# Gameboy_Cartridge.net
KiCad netlist of a schematic drawn in EAGLE
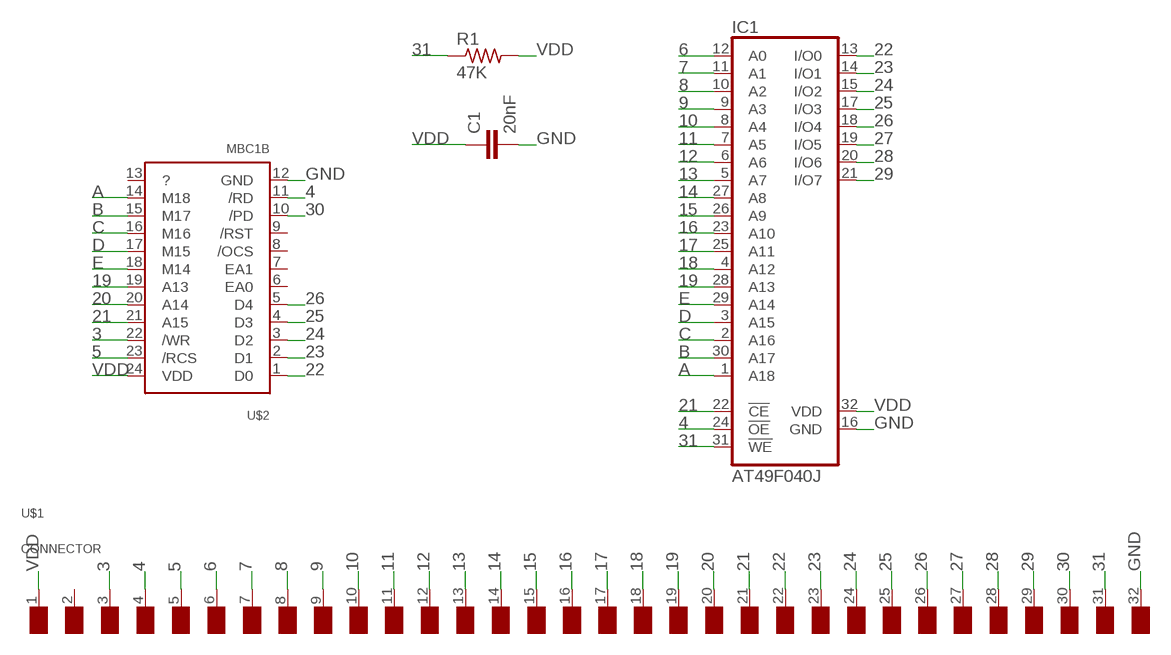
[diagram p0: schematic, sheet 1]

(export (version "E")
  (design (tool "Eeschema 10.0.6"))
  (components
    (comp (ref "C1")
      (value "20nF")
      (footprint "eagle-import:C0805")
      (libsource (lib "eagle-import") (part "C-EUC0805"))
    )
    (comp (ref "IC1")
      (value "AT49F040J")
      (footprint "eagle-import:PLCC32R")
      (libsource (lib "eagle-import") (part "AT49F040J"))
    )
    (comp (ref "R1")
      (value "47K")
      (footprint "eagle-import:M0805")
      (libsource (lib "eagle-import") (part "R-US_M0805"))
    )
    (comp (ref "U$1")
      (value "CONNECTOR")
      (footprint "eagle-import:CONNECTOR")
      (libsource (lib "eagle-import") (part "CONNECTOR"))
    )
    (comp (ref "U$2")
      (value "MBC1B")
      (footprint "eagle-import:MBC1B")
      (libsource (lib "eagle-import") (part "MBC1B"))
    )
  )
  (nets
    (net (code "1") (name "/3") (class "Default")
      (node (ref "U$1") (pin "3") (pinfunction "/WR_3") (pintype "bidirectional"))
      (node (ref "U$2") (pin "22") (pinfunction "/WR_22") (pintype "bidirectional"))
    )
    (net (code "2") (name "/4") (class "Default")
      (node (ref "IC1") (pin "24") (pinfunction "~{OE}_24") (pintype "input"))
      (node (ref "U$1") (pin "4") (pinfunction "/RD_4") (pintype "bidirectional"))
      (node (ref "U$2") (pin "11") (pinfunction "/RD_11") (pintype "bidirectional"))
    )
    (net (code "3") (name "/5") (class "Default")
      (node (ref "U$1") (pin "5") (pinfunction "/RCS_5") (pintype "bidirectional"))
      (node (ref "U$2") (pin "23") (pinfunction "/RCS_23") (pintype "bidirectional"))
    )
    (net (code "4") (name "/6") (class "Default")
      (node (ref "IC1") (pin "12") (pinfunction "A0_12") (pintype "input"))
      (node (ref "U$1") (pin "6") (pinfunction "A0_6") (pintype "bidirectional"))
    )
    (net (code "5") (name "/7") (class "Default")
      (node (ref "IC1") (pin "11") (pinfunction "A1_11") (pintype "input"))
      (node (ref "U$1") (pin "7") (pinfunction "A1_7") (pintype "bidirectional"))
    )
    (net (code "6") (name "/8") (class "Default")
      (node (ref "IC1") (pin "10") (pinfunction "A2_10") (pintype "input"))
      (node (ref "U$1") (pin "8") (pinfunction "A2_8") (pintype "bidirectional"))
    )
    (net (code "7") (name "/9") (class "Default")
      (node (ref "IC1") (pin "9") (pinfunction "A3_9") (pintype "input"))
      (node (ref "U$1") (pin "9") (pinfunction "A3_9") (pintype "bidirectional"))
    )
    (net (code "8") (name "/10") (class "Default")
      (node (ref "IC1") (pin "8") (pinfunction "A4_8") (pintype "input"))
      (node (ref "U$1") (pin "10") (pinfunction "A4_10") (pintype "bidirectional"))
    )
    (net (code "9") (name "/11") (class "Default")
      (node (ref "IC1") (pin "7") (pinfunction "A5_7") (pintype "input"))
      (node (ref "U$1") (pin "11") (pinfunction "A5_11") (pintype "bidirectional"))
    )
    (net (code "10") (name "/12") (class "Default")
      (node (ref "IC1") (pin "6") (pinfunction "A6_6") (pintype "input"))
      (node (ref "U$1") (pin "12") (pinfunction "A6_12") (pintype "bidirectional"))
    )
    (net (code "11") (name "/13") (class "Default")
      (node (ref "IC1") (pin "5") (pinfunction "A7_5") (pintype "input"))
      (node (ref "U$1") (pin "13") (pinfunction "A7_13") (pintype "bidirectional"))
    )
    (net (code "12") (name "/14") (class "Default")
      (node (ref "IC1") (pin "27") (pinfunction "A8_27") (pintype "input"))
      (node (ref "U$1") (pin "14") (pinfunction "A8_14") (pintype "bidirectional"))
    )
    (net (code "13") (name "/15") (class "Default")
      (node (ref "IC1") (pin "26") (pinfunction "A9_26") (pintype "input"))
      (node (ref "U$1") (pin "15") (pinfunction "A9_15") (pintype "bidirectional"))
    )
    (net (code "14") (name "/16") (class "Default")
      (node (ref "IC1") (pin "23") (pinfunction "A10_23") (pintype "input"))
      (node (ref "U$1") (pin "16") (pinfunction "A10_16") (pintype "bidirectional"))
    )
    (net (code "15") (name "/17") (class "Default")
      (node (ref "IC1") (pin "25") (pinfunction "A11_25") (pintype "input"))
      (node (ref "U$1") (pin "17") (pinfunction "A11_17") (pintype "bidirectional"))
    )
    (net (code "16") (name "/18") (class "Default")
      (node (ref "IC1") (pin "4") (pinfunction "A12_4") (pintype "input"))
      (node (ref "U$1") (pin "18") (pinfunction "A12_18") (pintype "bidirectional"))
    )
    (net (code "17") (name "/19") (class "Default")
      (node (ref "IC1") (pin "28") (pinfunction "A13_28") (pintype "input"))
      (node (ref "U$1") (pin "19") (pinfunction "A13_19") (pintype "bidirectional"))
      (node (ref "U$2") (pin "19") (pinfunction "A13_19") (pintype "bidirectional"))
    )
    (net (code "18") (name "/20") (class "Default")
      (node (ref "U$1") (pin "20") (pinfunction "A14_20") (pintype "bidirectional"))
      (node (ref "U$2") (pin "20") (pinfunction "A14_20") (pintype "bidirectional"))
    )
    (net (code "19") (name "/21") (class "Default")
      (node (ref "IC1") (pin "22") (pinfunction "~{CE}_22") (pintype "input"))
      (node (ref "U$1") (pin "21") (pinfunction "A15_21") (pintype "bidirectional"))
      (node (ref "U$2") (pin "21") (pinfunction "A15_21") (pintype "bidirectional"))
    )
    (net (code "20") (name "/22") (class "Default")
      (node (ref "IC1") (pin "13") (pinfunction "I/O0_13") (pintype "tri_state"))
      (node (ref "U$1") (pin "22") (pinfunction "D0_22") (pintype "bidirectional"))
      (node (ref "U$2") (pin "1") (pinfunction "D0_1") (pintype "bidirectional"))
    )
    (net (code "21") (name "/23") (class "Default")
      (node (ref "IC1") (pin "14") (pinfunction "I/O1_14") (pintype "tri_state"))
      (node (ref "U$1") (pin "23") (pinfunction "D1_23") (pintype "bidirectional"))
      (node (ref "U$2") (pin "2") (pinfunction "D1_2") (pintype "bidirectional"))
    )
    (net (code "22") (name "/24") (class "Default")
      (node (ref "IC1") (pin "15") (pinfunction "I/O2_15") (pintype "tri_state"))
      (node (ref "U$1") (pin "24") (pinfunction "D2_24") (pintype "bidirectional"))
      (node (ref "U$2") (pin "3") (pinfunction "D2_3") (pintype "bidirectional"))
    )
    (net (code "23") (name "/25") (class "Default")
      (node (ref "IC1") (pin "17") (pinfunction "I/O3_17") (pintype "tri_state"))
      (node (ref "U$1") (pin "25") (pinfunction "D3_25") (pintype "bidirectional"))
      (node (ref "U$2") (pin "4") (pinfunction "D3_4") (pintype "bidirectional"))
    )
    (net (code "24") (name "/26") (class "Default")
      (node (ref "IC1") (pin "18") (pinfunction "I/O4_18") (pintype "tri_state"))
      (node (ref "U$1") (pin "26") (pinfunction "D4_26") (pintype "bidirectional"))
      (node (ref "U$2") (pin "5") (pinfunction "D4_5") (pintype "bidirectional"))
    )
    (net (code "25") (name "/27") (class "Default")
      (node (ref "IC1") (pin "19") (pinfunction "I/O5_19") (pintype "tri_state"))
      (node (ref "U$1") (pin "27") (pinfunction "D5_27") (pintype "bidirectional"))
    )
    (net (code "26") (name "/28") (class "Default")
      (node (ref "IC1") (pin "20") (pinfunction "I/O6_20") (pintype "tri_state"))
      (node (ref "U$1") (pin "28") (pinfunction "D6_28") (pintype "bidirectional"))
    )
    (net (code "27") (name "/29") (class "Default")
      (node (ref "IC1") (pin "21") (pinfunction "I/O7_21") (pintype "tri_state"))
      (node (ref "U$1") (pin "29") (pinfunction "D7_29") (pintype "bidirectional"))
    )
    (net (code "28") (name "/30") (class "Default")
      (node (ref "U$1") (pin "30") (pinfunction "/RS_30") (pintype "bidirectional"))
      (node (ref "U$2") (pin "10") (pinfunction "/PD_10") (pintype "bidirectional"))
    )
    (net (code "29") (name "/31") (class "Default")
      (node (ref "IC1") (pin "31") (pinfunction "~{WE}_31") (pintype "input"))
      (node (ref "R1") (pin "1") (pinfunction "1_1") (pintype "passive"))
      (node (ref "U$1") (pin "31") (pinfunction "VIN_31") (pintype "bidirectional"))
    )
    (net (code "30") (name "/A") (class "Default")
      (node (ref "IC1") (pin "1") (pinfunction "A18_1") (pintype "input"))
      (node (ref "U$2") (pin "14") (pinfunction "M18_14") (pintype "bidirectional"))
    )
    (net (code "31") (name "/B") (class "Default")
      (node (ref "IC1") (pin "30") (pinfunction "A17_30") (pintype "input"))
      (node (ref "U$2") (pin "15") (pinfunction "M17_15") (pintype "bidirectional"))
    )
    (net (code "32") (name "/C") (class "Default")
      (node (ref "IC1") (pin "2") (pinfunction "A16_2") (pintype "input"))
      (node (ref "U$2") (pin "16") (pinfunction "M16_16") (pintype "bidirectional"))
    )
    (net (code "33") (name "/D") (class "Default")
      (node (ref "IC1") (pin "3") (pinfunction "A15_3") (pintype "input"))
      (node (ref "U$2") (pin "17") (pinfunction "M15_17") (pintype "bidirectional"))
    )
    (net (code "34") (name "/E") (class "Default")
      (node (ref "IC1") (pin "29") (pinfunction "A14_29") (pintype "input"))
      (node (ref "U$2") (pin "18") (pinfunction "M14_18") (pintype "bidirectional"))
    )
    (net (code "35") (name "/GND") (class "Default")
      (node (ref "C1") (pin "2") (pinfunction "2_2") (pintype "passive"))
      (node (ref "IC1") (pin "16") (pinfunction "GND_16") (pintype "power_in"))
      (node (ref "U$1") (pin "32") (pinfunction "GND_32") (pintype "power_in"))
      (node (ref "U$2") (pin "12") (pinfunction "GND_12") (pintype "power_in"))
    )
    (net (code "36") (name "/VDD") (class "Default")
      (node (ref "C1") (pin "1") (pinfunction "1_1") (pintype "passive"))
      (node (ref "IC1") (pin "32") (pinfunction "VDD_32") (pintype "power_in"))
      (node (ref "R1") (pin "2") (pinfunction "2_2") (pintype "passive"))
      (node (ref "U$1") (pin "1") (pinfunction "VDD_1") (pintype "power_in"))
      (node (ref "U$2") (pin "24") (pinfunction "VDD_24") (pintype "power_in"))
    )
    (net (code "37") (name "unconnected-(U$1-NC-Pad2)") (class "Default")
      (node (ref "U$1") (pin "2") (pinfunction "NC_2") (pintype "no_connect"))
    )
    (net (code "38") (name "unconnected-(U$2-?-Pad13)") (class "Default")
      (node (ref "U$2") (pin "13") (pinfunction "?_13") (pintype "bidirectional"))
    )
    (net (code "39") (name "unconnected-(U$2-EA0-Pad6)") (class "Default")
      (node (ref "U$2") (pin "6") (pinfunction "EA0_6") (pintype "bidirectional"))
    )
    (net (code "40") (name "unconnected-(U$2-EA1-Pad7)") (class "Default")
      (node (ref "U$2") (pin "7") (pinfunction "EA1_7") (pintype "bidirectional"))
    )
    (net (code "41") (name "unconnected-(U$2-{slash}OCS-Pad8)") (class "Default")
      (node (ref "U$2") (pin "8") (pinfunction "/OCS_8") (pintype "bidirectional"))
    )
    (net (code "42") (name "unconnected-(U$2-{slash}RST-Pad9)") (class "Default")
      (node (ref "U$2") (pin "9") (pinfunction "/RST_9") (pintype "bidirectional"))
    )
  )
)
